# 13-Fusing.net
KiCad netlist of a schematic drawn in Altium Designer
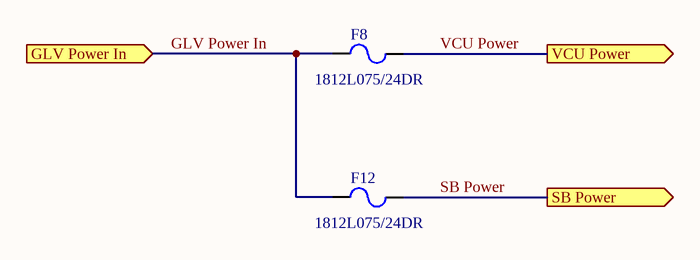
[diagram p0: 13-Fusing.SchDoc]

(export (version "E")
  (design (tool "Eeschema 10.0.6"))
  (components
    (comp (ref "F8")
      (value "1812L075/24DR")
      (footprint "LFUS-1812L07524DR_V")
      (description "Poly-Fuse(R) Resettable PTC, 24 V, 100 A, -40 to 85 degC, 2-Pin SMD, RoHS, Tape and Reel")
      (fields (field (name "MANUFACTURER") "Littelfuse"))
      (libsource (lib "Altium Content Vault") (part "FUSE-2"))
    )
    (comp (ref "F12")
      (value "1812L075/24DR")
      (footprint "LFUS-1812L07524DR_V")
      (description "Poly-Fuse(R) Resettable PTC, 24 V, 100 A, -40 to 85 degC, 2-Pin SMD, RoHS, Tape and Reel")
      (fields (field (name "MANUFACTURER") "Littelfuse"))
      (libsource (lib "Altium Content Vault") (part "FUSE-2"))
    )
  )
  (nets
    (net (code "1") (name "/GLV Power In") (class "Default")
      (node (ref "F12") (pin "1") (pinfunction "1_1") (pintype "passive"))
      (node (ref "F8") (pin "1") (pinfunction "1_1") (pintype "passive"))
    )
    (net (code "2") (name "/SB Power") (class "Default")
      (node (ref "F12") (pin "2") (pinfunction "2_2") (pintype "passive"))
    )
    (net (code "3") (name "/VCU Power") (class "Default")
      (node (ref "F8") (pin "2") (pinfunction "2_2") (pintype "passive"))
    )
  )
)
